# indication.net
KiCad netlist of a schematic drawn in Altium Designer
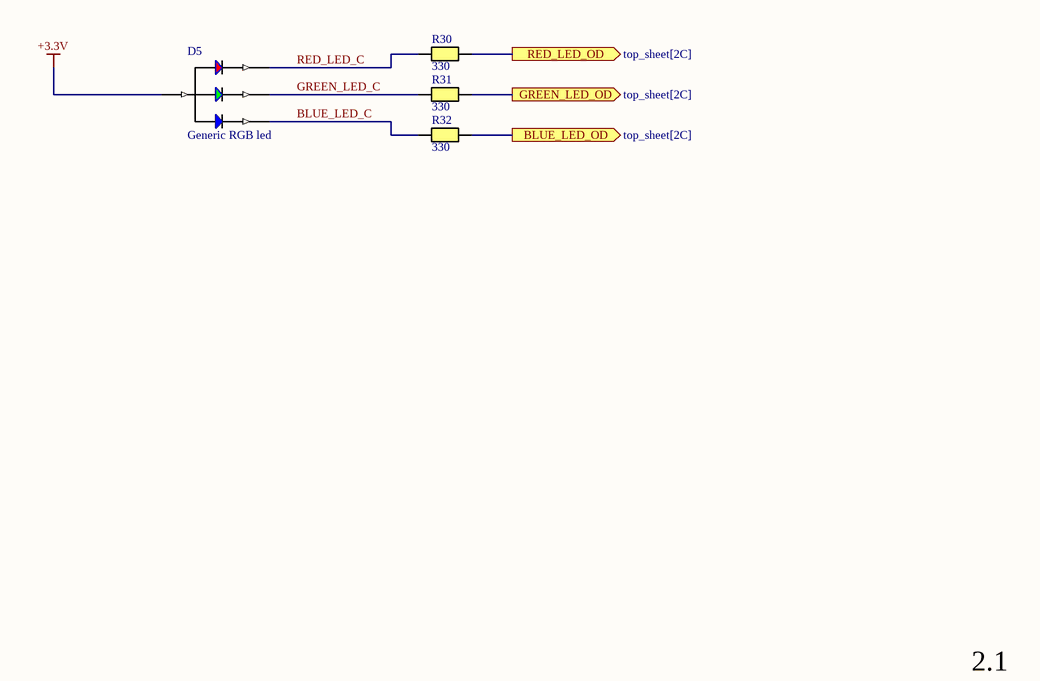
[diagram p0: indication.SchDoc]

(export (version "E")
  (design (tool "Eeschema 10.0.6"))
  (components
    (comp (ref "D5")
      (value "Generic RGB led")
      (footprint "RGB throu hole 90 deg")
      (libsource (lib "Optical") (part "RGB led"))
    )
    (comp (ref "R30")
      (value "330")
      (footprint "RESC0603(1608)_N")
      (description "Resistor Medium Density")
      (libsource (lib "Discrete") (part "Resistor M"))
    )
    (comp (ref "R31")
      (value "330")
      (footprint "RESC0603(1608)_N")
      (description "Resistor Medium Density")
      (libsource (lib "Discrete") (part "Resistor M"))
    )
    (comp (ref "R32")
      (value "330")
      (footprint "RESC0603(1608)_N")
      (description "Resistor Medium Density")
      (libsource (lib "Discrete") (part "Resistor M"))
    )
  )
  (nets
    (net (code "1") (name "+3.3V") (class "Default")
      (node (ref "D5") (pin "CA") (pinfunction "CA_CA") (pintype "input"))
    )
    (net (code "2") (name "/BLUE_LED_C") (class "Default")
      (node (ref "D5") (pin "BC") (pinfunction "BC_BC") (pintype "output"))
      (node (ref "R32") (pin "1") (pinfunction "1_1") (pintype "passive"))
    )
    (net (code "3") (name "/BLUE_LED_OD") (class "Default")
      (node (ref "R32") (pin "2") (pinfunction "2_2") (pintype "passive"))
    )
    (net (code "4") (name "/GREEN_LED_C") (class "Default")
      (node (ref "D5") (pin "GC") (pinfunction "GC_GC") (pintype "output"))
      (node (ref "R31") (pin "1") (pinfunction "1_1") (pintype "passive"))
    )
    (net (code "5") (name "/GREEN_LED_OD") (class "Default")
      (node (ref "R31") (pin "2") (pinfunction "2_2") (pintype "passive"))
    )
    (net (code "6") (name "/RED_LED_C") (class "Default")
      (node (ref "D5") (pin "RC") (pinfunction "RC_RC") (pintype "output"))
      (node (ref "R30") (pin "1") (pinfunction "1_1") (pintype "passive"))
    )
    (net (code "7") (name "/RED_LED_OD") (class "Default")
      (node (ref "R30") (pin "2") (pinfunction "2_2") (pintype "passive"))
    )
  )
)
